# RF_AMPL_001.net
KiCad netlist of a schematic drawn in Altium Designer
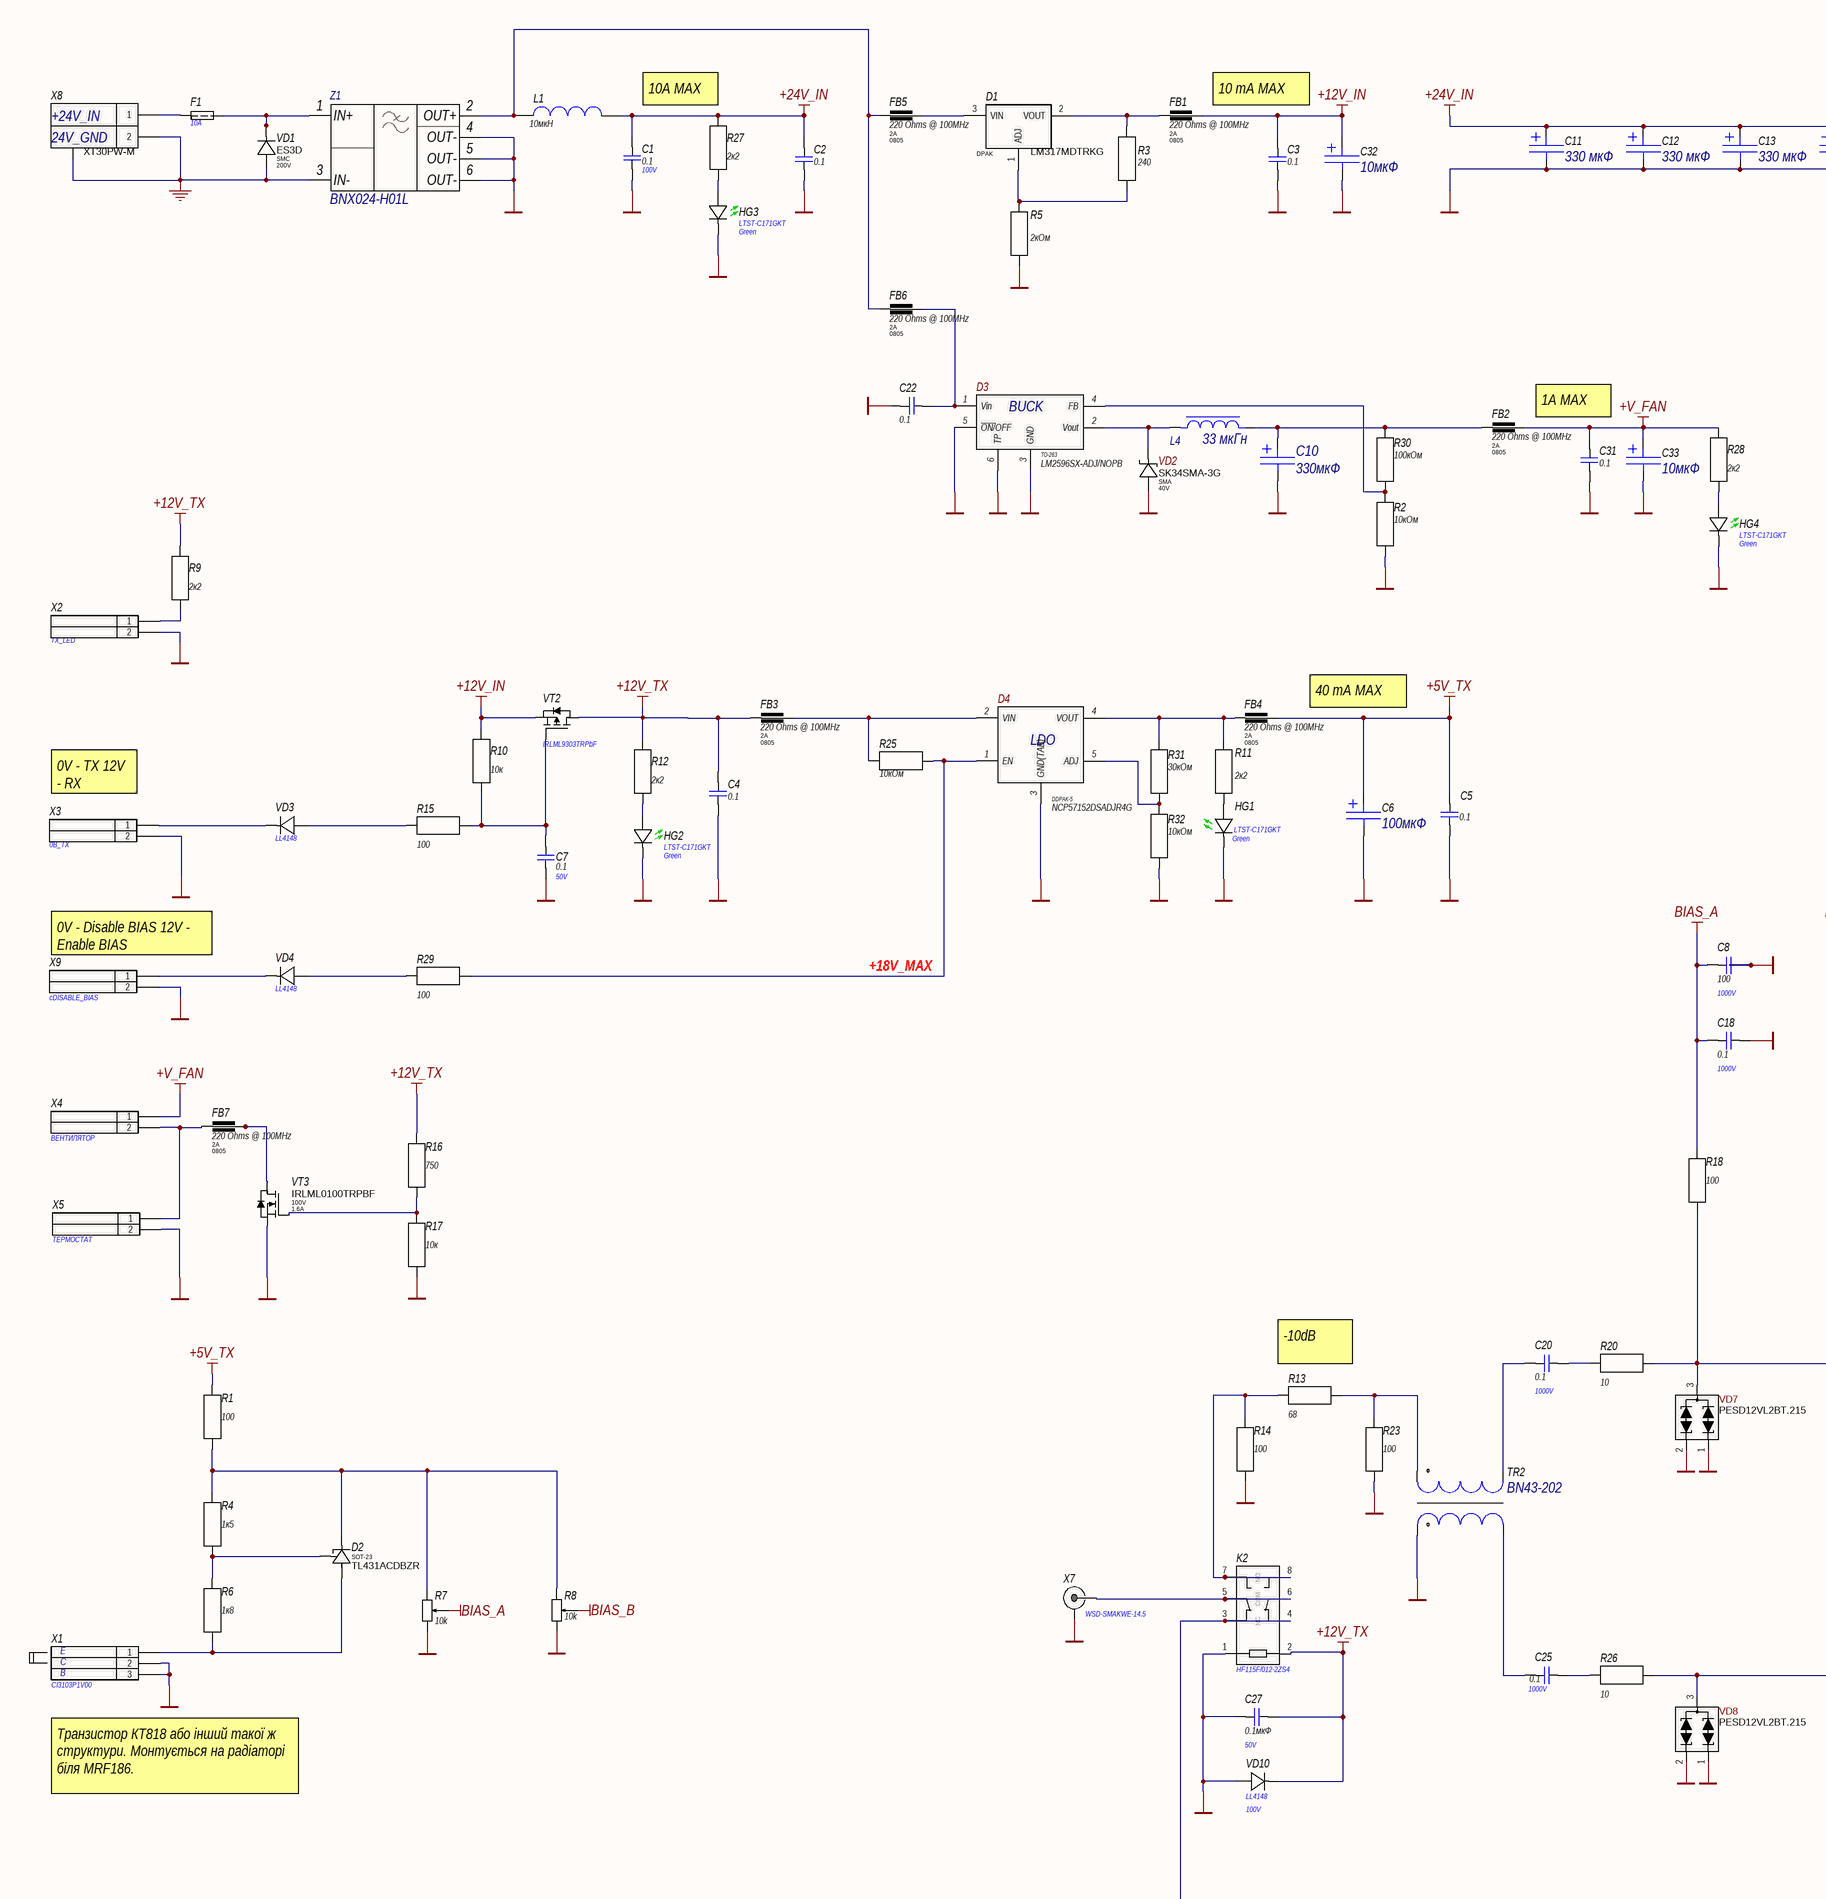
[diagram p0: RF_AMPL_001.SchDoc, left]
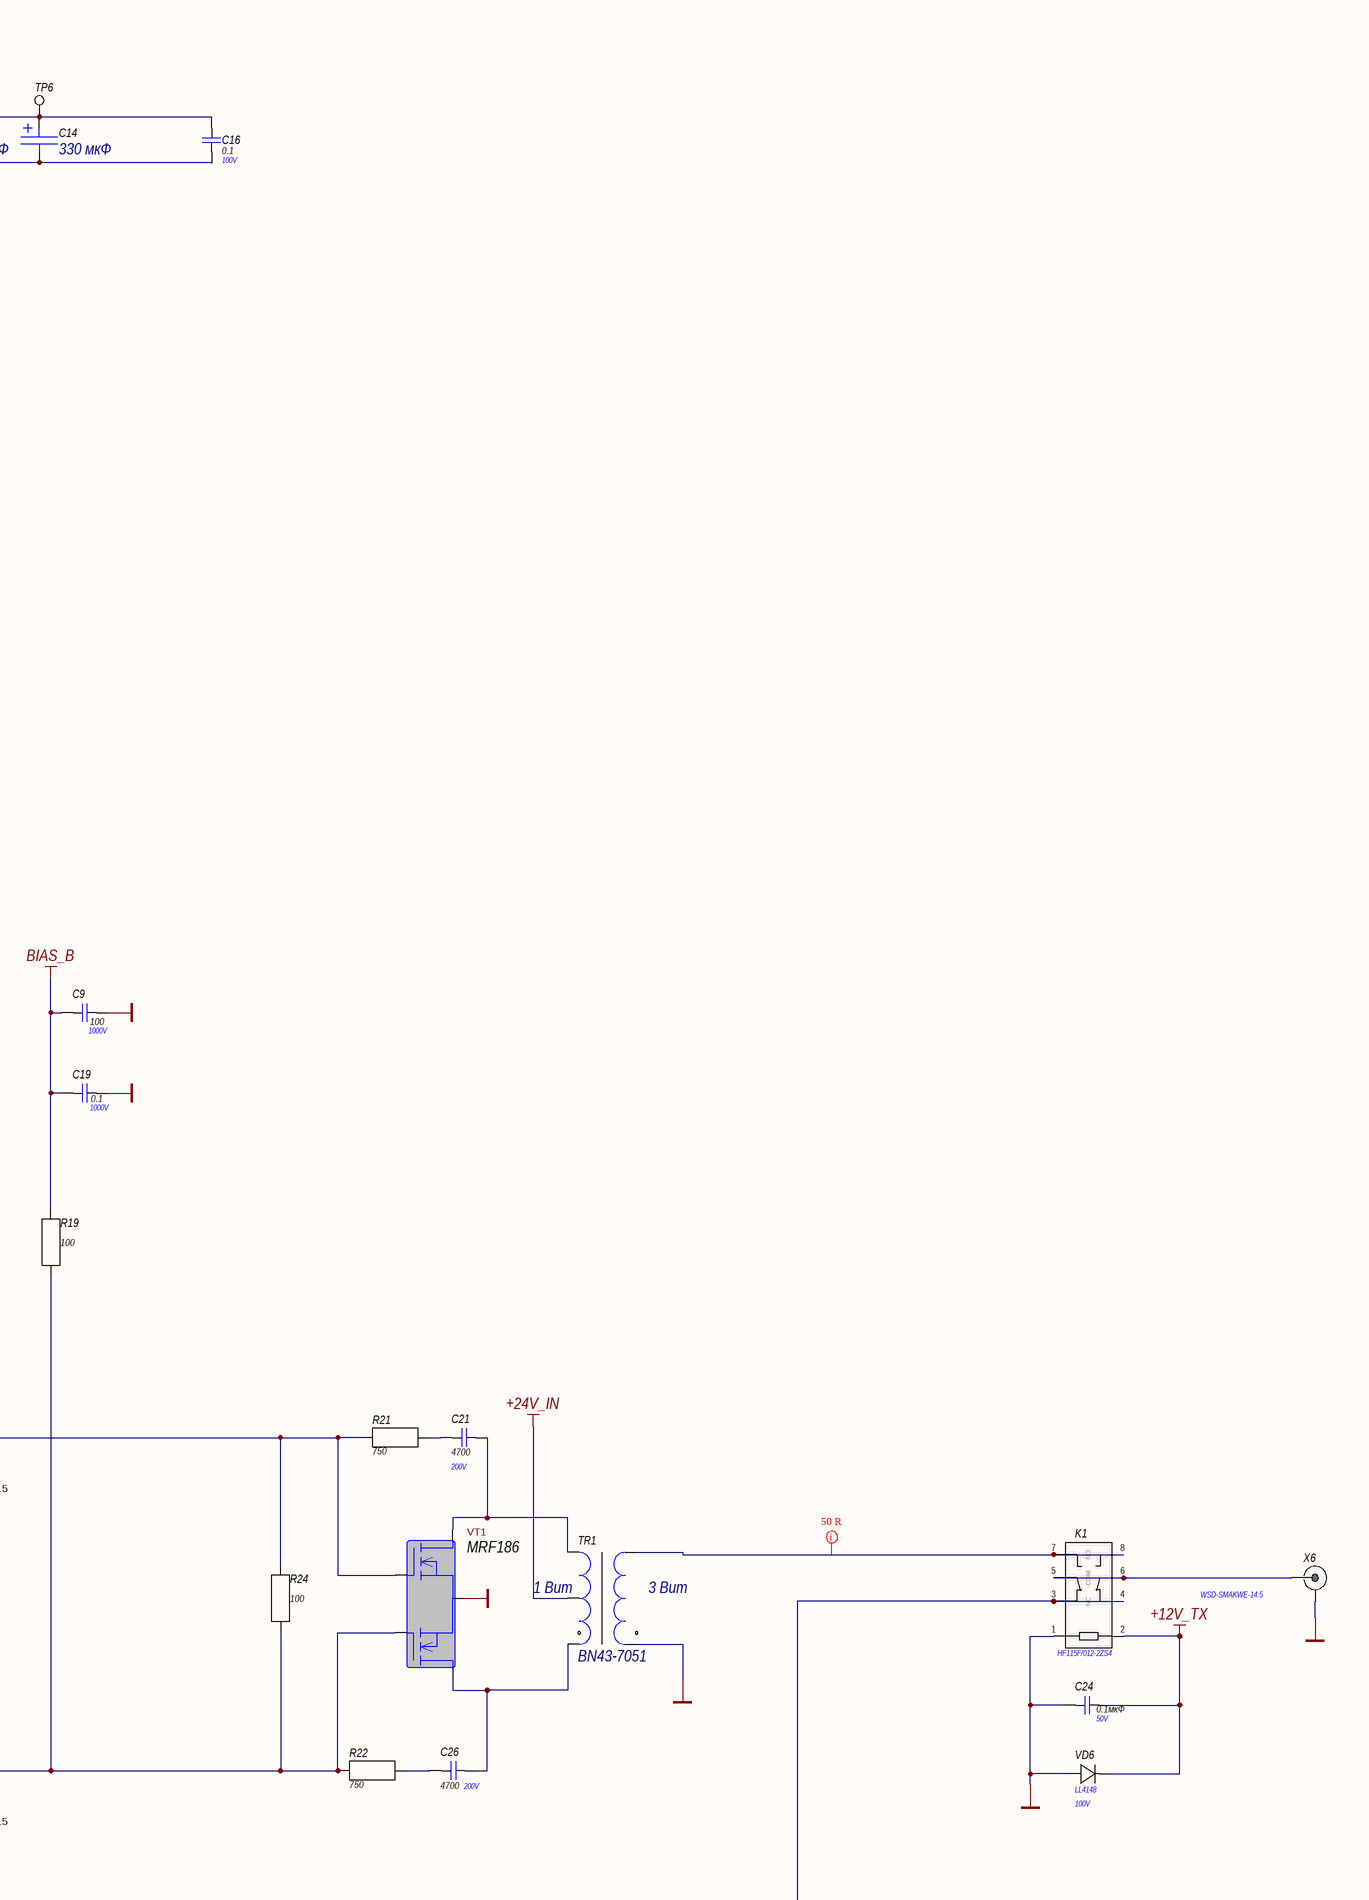
[diagram p1: RF_AMPL_001.SchDoc, right]

(export (version "E")
  (design (tool "Eeschema 10.0.6"))
  (components
    (comp (ref "C1")
      (value "0.1")
      (footprint "C_CERAMIC_1206_MED")
      (description "1nF 1000V X7R ±10% 1206 Ceramic Capacitor RoHS")
      (fields
        (field (name "VOLTAGE") "100V")
        (field (name "PART NUMBER") "1206B102K102CG")
        (field (name "MANUFACTURER") "Walsin")
      )
      (libsource (lib "vitech_capacitors") (part "1206B102K102CG"))
    )
    (comp (ref "C2")
      (value "0.1")
      (footprint "C_CERAMIC_1206_MED")
      (description "1nF 1000V X7R ±10% 1206 Ceramic Capacitor RoHS")
      (fields (field (name "VOLTAGE") "100V") (field (name "PART NUMBER") "1206B102K102CG"))
      (libsource (lib "vitech_capacitors") (part "1206B102K102CG"))
    )
    (comp (ref "C3")
      (value "0.1")
      (footprint "C_CERAMIC_1206_MED")
      (description "1nF 1000V X7R ±10% 1206 Ceramic Capacitor RoHS")
      (fields (field (name "VOLTAGE") "100V") (field (name "PART NUMBER") "1206B102K102CG"))
      (libsource (lib "vitech_capacitors") (part "1206B102K102CG"))
    )
    (comp (ref "C4")
      (value "0.1")
      (footprint "C_CERAMIC_1206_MED")
      (description "1nF 1000V X7R ±10% 1206 Ceramic Capacitor RoHS")
      (fields (field (name "VOLTAGE") "100V") (field (name "PART NUMBER") "1206B102K102CG"))
      (libsource (lib "vitech_capacitors") (part "1206B102K102CG"))
    )
    (comp (ref "C5")
      (value "0.1")
      (footprint "C_CERAMIC_1206_MED")
      (description "1nF 1000V X7R ±10% 1206 Ceramic Capacitor RoHS")
      (fields (field (name "VOLTAGE") "100V") (field (name "PART NUMBER") "1206B102K102CG"))
      (libsource (lib "vitech_capacitors") (part "1206B102K102CG"))
    )
    (comp (ref "C6")
      (value "100мкФ")
      (footprint "CAPM_CASE_D_7.3x4.3x3.1mm")
      (description "Capacitor Tantalum *pF ±*% *V Case D")
      (fields (field (name "MANUFACTURER") "AVX") (field (name "PART NUMBER") "TAJD107M016R"))
      (libsource (lib "Passive") (part "CAP_TANTALUM_POLAR_CASE_D"))
    )
    (comp (ref "C7")
      (value "0.1")
      (footprint "C_CERAMIC_1206_MED")
      (description "1nF 1000V X7R ±10% 1206 Ceramic Capacitor RoHS")
      (fields
        (field (name "VOLTAGE") "50V")
        (field (name "PART NUMBER") "1206B102K102CG")
        (field (name "MANUFACTURER") "Walsin")
      )
      (libsource (lib "vitech_capacitors") (part "1206B102K102CG"))
    )
    (comp (ref "C8")
      (value "100")
      (footprint "C_CERAMIC_1206_MED")
      (description "1nF 1000V X7R ±10% 1206 Ceramic Capacitor RoHS")
      (fields
        (field (name "VOLTAGE") "1000V")
        (field (name "PART NUMBER") "1206B102K102CG")
        (field (name "MANUFACTURER") "Walsin")
      )
      (libsource (lib "vitech_capacitors") (part "1206B102K102CG"))
    )
    (comp (ref "C9")
      (value "100")
      (footprint "C_CERAMIC_1206_MED")
      (description "1nF 1000V X7R ±10% 1206 Ceramic Capacitor RoHS")
      (fields
        (field (name "VOLTAGE") "1000V")
        (field (name "PART NUMBER") "1206B102K102CG")
        (field (name "MANUFACTURER") "Walsin")
      )
      (libsource (lib "vitech_capacitors") (part "1206B102K102CG"))
    )
    (comp (ref "C10")
      (value "330мкФ")
      (footprint "CAPA_CASE_F_Panasonic_FT")
      (description "Capacitor Electrolytic *pF ±*% *V Case F")
      (fields (field (name "MANUFACTURER") "Panasonic") (field (name "PART NUMBER") "EEEFK1C331P"))
      (libsource (lib "Passive") (part "CAP_ELECTROLYTIC_POLAR_CASE_F_Panasonic_FT"))
    )
    (comp (ref "C11")
      (value "330 мкФ")
      (footprint "CAPA_CASE_G_10.4x10.4x10.5mm")
      (description "Capacitor Electrolytic *pF ±*% *V Case G")
      (fields (field (name "TOLERANCE") "±*%") (field (name "VOLTAGE") "*В"))
      (libsource (lib "Passive") (part "CAP_ELECTROLYTIC_POLAR_CASE_G"))
    )
    (comp (ref "C12")
      (value "330 мкФ")
      (footprint "CAPA_CASE_G_10.4x10.4x10.5mm")
      (description "Capacitor Electrolytic *pF ±*% *V Case G")
      (fields (field (name "TOLERANCE") "±*%") (field (name "VOLTAGE") "*В"))
      (libsource (lib "Passive") (part "CAP_ELECTROLYTIC_POLAR_CASE_G"))
    )
    (comp (ref "C13")
      (value "330 мкФ")
      (footprint "CAPA_CASE_G_10.4x10.4x10.5mm")
      (description "Capacitor Electrolytic *pF ±*% *V Case G")
      (fields (field (name "TOLERANCE") "±*%") (field (name "VOLTAGE") "*В"))
      (libsource (lib "Passive") (part "CAP_ELECTROLYTIC_POLAR_CASE_G"))
    )
    (comp (ref "C14")
      (value "330 мкФ")
      (footprint "CAPA_CASE_G_10.4x10.4x10.5mm")
      (description "Capacitor Electrolytic *pF ±*% *V Case G")
      (fields (field (name "TOLERANCE") "±*%") (field (name "VOLTAGE") "*В"))
      (libsource (lib "Passive") (part "CAP_ELECTROLYTIC_POLAR_CASE_G"))
    )
    (comp (ref "C16")
      (value "0.1")
      (footprint "C_CERAMIC_1206_MED")
      (description "1nF 1000V X7R ±10% 1206 Ceramic Capacitor RoHS")
      (fields
        (field (name "VOLTAGE") "100V")
        (field (name "PART NUMBER") "1206B102K102CG")
        (field (name "MANUFACTURER") "Walsin")
      )
      (libsource (lib "vitech_capacitors") (part "1206B102K102CG"))
    )
    (comp (ref "C18")
      (value "0.1")
      (footprint "C_CERAMIC_1206_MED")
      (description "1nF 1000V X7R ±10% 1206 Ceramic Capacitor RoHS")
      (fields
        (field (name "VOLTAGE") "1000V")
        (field (name "PART NUMBER") "1206B102K102CG")
        (field (name "MANUFACTURER") "Walsin")
      )
      (libsource (lib "vitech_capacitors") (part "1206B102K102CG"))
    )
    (comp (ref "C19")
      (value "0.1")
      (footprint "C_CERAMIC_1206_MED")
      (description "1nF 1000V X7R ±10% 1206 Ceramic Capacitor RoHS")
      (fields
        (field (name "VOLTAGE") "1000V")
        (field (name "PART NUMBER") "1206B102K102CG")
        (field (name "MANUFACTURER") "Walsin")
      )
      (libsource (lib "vitech_capacitors") (part "1206B102K102CG"))
    )
    (comp (ref "C20")
      (value "0.1")
      (footprint "C_CERAMIC_1206_MED")
      (description "1nF 1000V X7R ±10% 1206 Ceramic Capacitor RoHS")
      (fields
        (field (name "VOLTAGE") "1000V")
        (field (name "PART NUMBER") "1206B102K102CG")
        (field (name "MANUFACTURER") "Walsin")
      )
      (libsource (lib "vitech_capacitors") (part "1206B102K102CG"))
    )
    (comp (ref "C21")
      (value "4700")
      (footprint "C_CERAMIC_1206_MED")
      (description "1nF 1000V X7R ±10% 1206 Ceramic Capacitor RoHS")
      (fields
        (field (name "VOLTAGE") "200V")
        (field (name "PART NUMBER") "12065A472JAT2A")
        (field (name "MANUFACTURER") "Walsin")
      )
      (libsource (lib "vitech_capacitors") (part "1206B102K102CG"))
    )
    (comp (ref "C22")
      (value "0.1")
      (footprint "C_CERAMIC_1206_MED")
      (description "1nF 1000V X7R ±10% 1206 Ceramic Capacitor RoHS")
      (fields (field (name "VOLTAGE") "100V") (field (name "PART NUMBER") "1206B102K102CG"))
      (libsource (lib "vitech_capacitors") (part "1206B102K102CG"))
    )
    (comp (ref "C24")
      (value "0.1мкФ")
      (footprint "C_CERAMIC_0805_HI")
      (fields
        (field (name "PART NUMBER") "**")
        (field (name "MANUFACTURER") "Hitano")
        (field (name "TOLERANCE") "±5%")
        (field (name "VOLTAGE") "50V")
      )
      (libsource (lib "vitech_capacitors") (part "CERAMIC_0805"))
    )
    (comp (ref "C25")
      (value "0.1")
      (footprint "C_CERAMIC_1206_MED")
      (description "1nF 1000V X7R ±10% 1206 Ceramic Capacitor RoHS")
      (fields
        (field (name "VOLTAGE") "1000V")
        (field (name "PART NUMBER") "1206B102K102CG")
        (field (name "MANUFACTURER") "Walsin")
      )
      (libsource (lib "vitech_capacitors") (part "1206B102K102CG"))
    )
    (comp (ref "C26")
      (value "4700")
      (footprint "C_CERAMIC_1206_MED")
      (description "1nF 1000V X7R ±10% 1206 Ceramic Capacitor RoHS")
      (fields
        (field (name "VOLTAGE") "200V")
        (field (name "PART NUMBER") "12065A472JAT2A")
        (field (name "MANUFACTURER") "Walsin")
      )
      (libsource (lib "vitech_capacitors") (part "1206B102K102CG"))
    )
    (comp (ref "C27")
      (value "0.1мкФ")
      (footprint "C_CERAMIC_0805_HI")
      (fields
        (field (name "PART NUMBER") "**")
        (field (name "MANUFACTURER") "Hitano")
        (field (name "TOLERANCE") "±5%")
        (field (name "VOLTAGE") "50V")
      )
      (libsource (lib "vitech_capacitors") (part "CERAMIC_0805"))
    )
    (comp (ref "C31")
      (value "0.1")
      (footprint "C_CERAMIC_1206_MED")
      (description "1nF 1000V X7R ±10% 1206 Ceramic Capacitor RoHS")
      (fields (field (name "VOLTAGE") "100V") (field (name "PART NUMBER") "1206B102K102CG"))
      (libsource (lib "vitech_capacitors") (part "1206B102K102CG"))
    )
    (comp (ref "C32")
      (value "10мкФ")
      (footprint "CAPM_CASE_B_3.5x2.8x2.1mm")
      (description "Capacitor Tantalum *pF ±*% *V Case B")
      (fields (field (name "TOLERANCE") "±*%") (field (name "VOLTAGE") "20"))
      (libsource (lib "Passive") (part "CAP_TANTALUM_POLAR_CASE_B"))
    )
    (comp (ref "C33")
      (value "10мкФ")
      (footprint "CAPM_CASE_B_3.5x2.8x2.1mm")
      (description "Capacitor Tantalum *pF ±*% *V Case B")
      (fields (field (name "TOLERANCE") "±*%") (field (name "VOLTAGE") "20"))
      (libsource (lib "Passive") (part "CAP_TANTALUM_POLAR_CASE_B"))
    )
    (comp (ref "D1")
      (value "LM317MDTRKG")
      (footprint "DPAK")
      (description "4.25V to 40V Input Linear Voltage Regulator, 1 Output 500mA, Adjustable, TO-252-3 (DPAK)")
      (fields
        (field (name "MANUFACTURER") "Onsemi")
        (field (name "PACKAGE") "DPAK")
        (field (name "PART NUMBER") "LM317MDTRKG")
      )
      (libsource (lib "vitech_ic") (part "LM317MDTRKG"))
    )
    (comp (ref "D2")
      (value "TL431ACDBZR")
      (footprint "SOT-23_MED")
      (description "Adjustable Precision Shunt Regulator, Accuracy 1%,  SOT-23-3")
      (fields
        (field (name "PACKAGE") "SOT-23")
        (field (name "PART NUMBER") "TL431ACDBZR")
        (field (name "MANUFACTURER") "Texas Instruments")
      )
      (libsource (lib "vitech_ic") (part "TL431ACDBZR"))
    )
    (comp (ref "D3")
      (value "LM2596SX-ADJ/NOPB")
      (footprint "TO-263-5-1")
      (description "SIMPLE SWITCHER Power Converter 150-kHz 3-A Step-Down Voltage Regulator")
      (fields
        (field (name "MANUFACTURER") "Texas Instruments")
        (field (name "PACKAGE") "TO-263")
        (field (name "PART NUMBER") "LM2596SX-ADJ/NOPB")
      )
      (libsource (lib "vitech_ic") (part "LM2596SX-ADJ/NOPB"))
    )
    (comp (ref "D4")
      (value "NCP57152DSADJR4G")
      (footprint "DDPAK-5")
      (description "1.24V to 13V Input Low Dropout Regulator, Adjustable, 1.5A, D2PAK-5")
      (fields
        (field (name "PACKAGE") "DDPAK-5")
        (field (name "PART NUMBER") "NCP57152DSADJR4G")
        (field (name "MANUFACTURER") "Onsemi")
      )
      (libsource (lib "vitech_ic") (part "NCP57152DSADJR4G"))
    )
    (comp (ref "F1")
      (value "STANDART_FUSE_HOLDER")
      (footprint "17861640001")
      (description "Automotive Fuse holder THT-Mount")
      (fields (field (name "MANUFACTURER_PART_NUMBER") "17861640001") (field (name "CURRENT") "10A"))
      (libsource (lib "vitech_fuses") (part "STANDART_FUSE_HOLDER"))
    )
    (comp (ref "FB1")
      (value "220 Ohms @ 100MHz")
      (footprint "BLM21PGxxxxN1-Series")
      (description "220 Ohms @ 100MHz Power Line Ferrite Bead 0805, 2A 45mOhm")
      (fields
        (field (name "CURRENT") "2A")
        (field (name "PACKAGE") "0805")
        (field (name "PART NUMBER") "BLM21PG221SN1D")
        (field (name "TOLERANCE") "±25%")
      )
      (libsource (lib "vitech_inductors") (part "BLM21PG221SN1D"))
    )
    (comp (ref "FB2")
      (value "220 Ohms @ 100MHz")
      (footprint "BLM21PGxxxxN1-Series")
      (description "220 Ohms @ 100MHz Power Line Ferrite Bead 0805, 2A 45mOhm")
      (fields
        (field (name "CURRENT") "2A")
        (field (name "PACKAGE") "0805")
        (field (name "PART NUMBER") "BLM21PG221SN1D")
        (field (name "TOLERANCE") "±25%")
      )
      (libsource (lib "vitech_inductors") (part "BLM21PG221SN1D"))
    )
    (comp (ref "FB3")
      (value "220 Ohms @ 100MHz")
      (footprint "BLM21PGxxxxN1-Series")
      (description "220 Ohms @ 100MHz Power Line Ferrite Bead 0805, 2A 45mOhm")
      (fields
        (field (name "CURRENT") "2A")
        (field (name "PACKAGE") "0805")
        (field (name "PART NUMBER") "BLM21PG221SN1D")
        (field (name "TOLERANCE") "±25%")
      )
      (libsource (lib "vitech_inductors") (part "BLM21PG221SN1D"))
    )
    (comp (ref "FB4")
      (value "220 Ohms @ 100MHz")
      (footprint "BLM21PGxxxxN1-Series")
      (description "220 Ohms @ 100MHz Power Line Ferrite Bead 0805, 2A 45mOhm")
      (fields
        (field (name "CURRENT") "2A")
        (field (name "PACKAGE") "0805")
        (field (name "PART NUMBER") "BLM21PG221SN1D")
        (field (name "TOLERANCE") "±25%")
      )
      (libsource (lib "vitech_inductors") (part "BLM21PG221SN1D"))
    )
    (comp (ref "FB5")
      (value "220 Ohms @ 100MHz")
      (footprint "BLM21PGxxxxN1-Series")
      (description "220 Ohms @ 100MHz Power Line Ferrite Bead 0805, 2A 45mOhm")
      (fields
        (field (name "CURRENT") "2A")
        (field (name "PACKAGE") "0805")
        (field (name "PART NUMBER") "BLM21PG221SN1D")
        (field (name "TOLERANCE") "±25%")
      )
      (libsource (lib "vitech_inductors") (part "BLM21PG221SN1D"))
    )
    (comp (ref "FB6")
      (value "220 Ohms @ 100MHz")
      (footprint "BLM21PGxxxxN1-Series")
      (description "220 Ohms @ 100MHz Power Line Ferrite Bead 0805, 2A 45mOhm")
      (fields
        (field (name "CURRENT") "2A")
        (field (name "PACKAGE") "0805")
        (field (name "PART NUMBER") "BLM21PG221SN1D")
        (field (name "TOLERANCE") "±25%")
      )
      (libsource (lib "vitech_inductors") (part "BLM21PG221SN1D"))
    )
    (comp (ref "FB7")
      (value "220 Ohms @ 100MHz")
      (footprint "BLM21PGxxxxN1-Series")
      (description "220 Ohms @ 100MHz Power Line Ferrite Bead 0805, 2A 45mOhm")
      (fields
        (field (name "CURRENT") "2A")
        (field (name "PACKAGE") "0805")
        (field (name "PART NUMBER") "BLM21PG221SN1D")
        (field (name "TOLERANCE") "±25%")
      )
      (libsource (lib "vitech_inductors") (part "BLM21PG221SN1D"))
    )
    (comp (ref "HG1")
      (value "LTST-C171GKT")
      (footprint "LTST-C171GKT")
      (description "Low Power LED, Green 565nm, Clear, SMD 0805, Vf 2.1V - 2.6V, 5 ~ 12mcd @ 20 mA, 130°")
      (fields
        (field (name "PART NUMBER") "LTST-C171GKT")
        (field (name "COLOR") "Green")
        (field (name "MANUFACTURER") "Lite-On Optoelectronics")
      )
      (libsource (lib "vitech_opto") (part "LTST-C171GKT"))
    )
    (comp (ref "HG2")
      (value "LTST-C171GKT")
      (footprint "LTST-C171GKT")
      (description "Low Power LED, Green 565nm, Clear, SMD 0805, Vf 2.1V - 2.6V, 5 ~ 12mcd @ 20 mA, 130°")
      (fields
        (field (name "PART NUMBER") "LTST-C171GKT")
        (field (name "COLOR") "Green")
        (field (name "MANUFACTURER") "Lite-On Optoelectronics")
      )
      (libsource (lib "vitech_opto") (part "LTST-C171GKT"))
    )
    (comp (ref "HG3")
      (value "LTST-C171GKT")
      (footprint "LTST-C171GKT")
      (description "Low Power LED, Green 565nm, Clear, SMD 0805, Vf 2.1V - 2.6V, 5 ~ 12mcd @ 20 mA, 130°")
      (fields
        (field (name "PART NUMBER") "LTST-C171GKT")
        (field (name "COLOR") "Green")
        (field (name "MANUFACTURER") "Lite-On Optoelectronics")
      )
      (libsource (lib "vitech_opto") (part "LTST-C171GKT"))
    )
    (comp (ref "HG4")
      (value "LTST-C171GKT")
      (footprint "LTST-C171GKT")
      (description "Low Power LED, Green 565nm, Clear, SMD 0805, Vf 2.1V - 2.6V, 5 ~ 12mcd @ 20 mA, 130°")
      (fields
        (field (name "PART NUMBER") "LTST-C171GKT")
        (field (name "COLOR") "Green")
        (field (name "MANUFACTURER") "Lite-On Optoelectronics")
      )
      (libsource (lib "vitech_opto") (part "LTST-C171GKT"))
    )
    (comp (ref "K1")
      (value "HF115F/012-2ZS4")
      (footprint "HF115Fxxx-1(2)Zx3(4)")
      (description "Miniature High Power Relay, DPDT (2 Form C), 12VDC 400mW Coil, 5.0mm 2 Pole 8A AgCdO")
      (fields (field (name "PART NUMBER") "HF115F/012-2ZS4") (field (name "MANUFACTURER") "Hongfa"))
      (libsource (lib "vitech_electromechanics") (part "HF115F/012-2ZS4"))
    )
    (comp (ref "K2")
      (value "HF115F/012-2ZS4")
      (footprint "HF115Fxxx-1(2)Zx3(4)")
      (description "Miniature High Power Relay, DPDT (2 Form C), 12VDC 400mW Coil, 5.0mm 2 Pole 8A AgCdO")
      (fields (field (name "PART NUMBER") "HF115F/012-2ZS4") (field (name "MANUFACTURER") "Hongfa"))
      (libsource (lib "vitech_electromechanics") (part "HF115F/012-2ZS4"))
    )
    (comp (ref "L1")
      (value "10мкH")
      (footprint "IND: R22.9/14/7.62 (H)")
      (fields
        (field (name "MANUFACTURER") "Magnetics")
        (field (name "PARTNUMBER") "0077310A7")
        (field (name "VALUEMANUFACTURERPARTNUMBER") "Fixed inductor, 10мкH, ±20%, R22.9/14/7.62, Kool Mu, µ=125, 90 нГн/витков2")
      )
      (libsource (lib "inductor") (part "Inductor_R22.9/14/7.62"))
    )
    (comp (ref "L4")
      (value "33 мкГн")
      (footprint "INDPWR_Sumida_CDRH127/LD_INDM120120X80N")
      (description "FIXED IND  UH   A  MOHM SMD")
      (fields (field (name "MANUFACTURER") "Sumida") (field (name "PART NUMBER") "CDRH127/LD"))
      (libsource (lib "Passive") (part "INDPWR_Sumida_CDRH127/LD"))
    )
    (comp (ref "R1")
      (value "100")
      (footprint "R_ANY_CHIP_0805_HI")
      (description "RES 0.47 OHM 1% 1/8W 0805")
      (fields
        (field (name "MANUFACTURER") "Panasonic Electronic Components")
        (field (name "PART NUMBER") "ERJ-3RQFR47V")
      )
      (libsource (lib "") (part "RES_0805_2"))
    )
    (comp (ref "R2")
      (value "10кОм")
      (footprint "R_ANY_CHIP_0805_HI")
      (description "RES 0.47 OHM 1% 1/8W 0805")
      (fields
        (field (name "MANUFACTURER") "Panasonic Electronic Components")
        (field (name "PART NUMBER") "ERJ-3RQFR47V")
      )
      (libsource (lib "") (part "RES_0805_2"))
    )
    (comp (ref "R3")
      (value "240")
      (footprint "R_ANY_CHIP_0805_HI")
      (description "RES 0.47 OHM 1% 1/8W 0805")
      (fields
        (field (name "MANUFACTURER") "Panasonic Electronic Components")
        (field (name "PART NUMBER") "ERJ-3RQFR47V")
      )
      (libsource (lib "") (part "RES_0805_3"))
    )
    (comp (ref "R4")
      (value "1к5")
      (footprint "R_ANY_CHIP_0805_HI")
      (description "RES 0.47 OHM 1% 1/8W 0805")
      (fields
        (field (name "MANUFACTURER") "Panasonic Electronic Components")
        (field (name "PART NUMBER") "ERJ-3RQFR47V")
      )
      (libsource (lib "") (part "RES_0805_2"))
    )
    (comp (ref "R5")
      (value "2кОм")
      (footprint "R_ANY_CHIP_0805_HI")
      (description "RES 0.47 OHM 1% 1/8W 0805")
      (fields
        (field (name "MANUFACTURER") "Panasonic Electronic Components")
        (field (name "PART NUMBER") "ERJ-3RQFR47V")
      )
      (libsource (lib "") (part "RES_0805_3"))
    )
    (comp (ref "R6")
      (value "1к8")
      (footprint "R_ANY_CHIP_0805_HI")
      (description "RES 0.47 OHM 1% 1/8W 0805")
      (fields
        (field (name "MANUFACTURER") "Panasonic Electronic Components")
        (field (name "PART NUMBER") "ERJ-3RQFR47V")
      )
      (libsource (lib "") (part "RES_0805_2"))
    )
    (comp (ref "R7")
      (value "10k")
      (footprint "3296W-1-xxx")
      (description "10 kOhms ±10% Trimmer Resistor, 0.5W, Through Hole 3/8\", 4.83x9.53mm, 10.03mm Height")
      (fields (field (name "TOLERANCE") "±10%") (field (name "PART NUMBER") "3296W-1-103LF"))
      (libsource (lib "resistors") (part "3296W-1-103LF"))
    )
    (comp (ref "R8")
      (value "10k")
      (footprint "3296W-1-xxx")
      (description "10 kOhms ±10% Trimmer Resistor, 0.5W, Through Hole 3/8\", 4.83x9.53mm, 10.03mm Height")
      (fields (field (name "TOLERANCE") "±10%") (field (name "PART NUMBER") "3296W-1-103LF"))
      (libsource (lib "resistors") (part "3296W-1-103LF"))
    )
    (comp (ref "R9")
      (value "2к2")
      (footprint "R_ANY_CHIP_0805_HI")
      (description "RES 0.47 OHM 1% 1/8W 0805")
      (fields
        (field (name "MANUFACTURER") "Panasonic Electronic Components")
        (field (name "PART NUMBER") "ERJ-3RQFR47V")
      )
      (libsource (lib "") (part "RES_0805_3"))
    )
    (comp (ref "R10")
      (value "10к")
      (footprint "R_ANY_CHIP_0805_HI")
      (description "RES 0.47 OHM 1% 1/8W 0805")
      (fields
        (field (name "MANUFACTURER") "Panasonic Electronic Components")
        (field (name "PART NUMBER") "ERJ-3RQFR47V")
      )
      (libsource (lib "") (part "RES_0805_3"))
    )
    (comp (ref "R11")
      (value "2к2")
      (footprint "R_ANY_CHIP_0805_HI")
      (description "RES 0.47 OHM 1% 1/8W 0805")
      (fields
        (field (name "MANUFACTURER") "Panasonic Electronic Components")
        (field (name "PART NUMBER") "ERJ-3RQFR47V")
      )
      (libsource (lib "") (part "RES_0805_3"))
    )
    (comp (ref "R12")
      (value "2к2")
      (footprint "R_ANY_CHIP_0805_HI")
      (description "RES 0.47 OHM 1% 1/8W 0805")
      (fields
        (field (name "MANUFACTURER") "Panasonic Electronic Components")
        (field (name "PART NUMBER") "ERJ-3RQFR47V")
      )
      (libsource (lib "") (part "RES_0805_2"))
    )
    (comp (ref "R13")
      (value "68")
      (footprint "FKN2WS-Series")
      (description "RESISTORS THT")
      (fields
        (field (name "MANUFACTURER") "Panasonic Electronic Components")
        (field (name "PART NUMBER") "ERJ-3RQFR47V")
      )
      (libsource (lib "") (part "RES_THT_1"))
    )
    (comp (ref "R14")
      (value "100")
      (footprint "FKN2WS-Series")
      (description "RESISTORS THT")
      (fields
        (field (name "MANUFACTURER") "Panasonic Electronic Components")
        (field (name "PART NUMBER") "ERJ-3RQFR47V")
      )
      (libsource (lib "") (part "RES_THT_2"))
    )
    (comp (ref "R15")
      (value "100")
      (footprint "R_ANY_CHIP_0805_HI")
      (description "RES 0.47 OHM 1% 1/8W 0805")
      (fields
        (field (name "MANUFACTURER") "Panasonic Electronic Components")
        (field (name "PART NUMBER") "ERJ-3RQFR47V")
      )
      (libsource (lib "") (part "RES_0805_1"))
    )
    (comp (ref "R16")
      (value "750")
      (footprint "R_ANY_CHIP_0805_HI")
      (description "RES 0.47 OHM 1% 1/8W 0805")
      (fields
        (field (name "MANUFACTURER") "Panasonic Electronic Components")
        (field (name "PART NUMBER") "ERJ-3RQFR47V")
      )
      (libsource (lib "") (part "RES_0805_2"))
    )
    (comp (ref "R17")
      (value "10к")
      (footprint "R_ANY_CHIP_0805_HI")
      (description "RES 0.47 OHM 1% 1/8W 0805")
      (fields
        (field (name "MANUFACTURER") "Panasonic Electronic Components")
        (field (name "PART NUMBER") "ERJ-3RQFR47V")
      )
      (libsource (lib "") (part "RES_0805_3"))
    )
    (comp (ref "R18")
      (value "100")
      (footprint "R_ANY_CHIP_0805_HI")
      (description "RES 0.47 OHM 1% 1/8W 0805")
      (fields
        (field (name "MANUFACTURER") "Panasonic Electronic Components")
        (field (name "PART NUMBER") "ERJ-3RQFR47V")
      )
      (libsource (lib "") (part "RES_0805_2"))
    )
    (comp (ref "R19")
      (value "100")
      (footprint "R_ANY_CHIP_0805_HI")
      (description "RES 0.47 OHM 1% 1/8W 0805")
      (fields
        (field (name "MANUFACTURER") "Panasonic Electronic Components")
        (field (name "PART NUMBER") "ERJ-3RQFR47V")
      )
      (libsource (lib "") (part "RES_0805_2"))
    )
    (comp (ref "R20")
      (value "10")
      (footprint "R_ANY_CHIP_0805_HI")
      (description "RES 0.47 OHM 1% 1/8W 0805")
      (fields
        (field (name "MANUFACTURER") "Panasonic Electronic Components")
        (field (name "PART NUMBER") "ERJ-3RQFR47V")
      )
      (libsource (lib "vitech_resistors") (part "RES_0805"))
    )
    (comp (ref "R21")
      (value "750")
      (footprint "FKN2WS-Series")
      (description "RESISTORS THT")
      (fields
        (field (name "MANUFACTURER") "Panasonic Electronic Components")
        (field (name "PART NUMBER") "ERJ-3RQFR47V")
      )
      (libsource (lib "vitech_resistors") (part "RES_THT"))
    )
    (comp (ref "R22")
      (value "750")
      (footprint "FKN2WS-Series")
      (description "RESISTORS THT")
      (fields
        (field (name "MANUFACTURER") "Panasonic Electronic Components")
        (field (name "PART NUMBER") "ERJ-3RQFR47V")
      )
      (libsource (lib "vitech_resistors") (part "RES_THT"))
    )
    (comp (ref "R23")
      (value "100")
      (footprint "FKN2WS-Series")
      (description "RESISTORS THT")
      (fields
        (field (name "MANUFACTURER") "Panasonic Electronic Components")
        (field (name "PART NUMBER") "ERJ-3RQFR47V")
      )
      (libsource (lib "") (part "RES_THT_2"))
    )
    (comp (ref "R24")
      (value "100")
      (footprint "FKN2WS-Series")
      (description "RESISTORS THT")
      (fields
        (field (name "MANUFACTURER") "Panasonic Electronic Components")
        (field (name "PART NUMBER") "ERJ-3RQFR47V")
      )
      (libsource (lib "") (part "RES_THT_2"))
    )
    (comp (ref "R25")
      (value "10кОм")
      (footprint "R_ANY_CHIP_0805_HI")
      (description "RES 0.47 OHM 1% 1/8W 0805")
      (fields
        (field (name "MANUFACTURER") "Panasonic Electronic Components")
        (field (name "PART NUMBER") "ERJ-3RQFR47V")
      )
      (libsource (lib "vitech_resistors") (part "RES_0805"))
    )
    (comp (ref "R26")
      (value "10")
      (footprint "R_ANY_CHIP_0805_HI")
      (description "RES 0.47 OHM 1% 1/8W 0805")
      (fields
        (field (name "MANUFACTURER") "Panasonic Electronic Components")
        (field (name "PART NUMBER") "ERJ-3RQFR47V")
      )
      (libsource (lib "vitech_resistors") (part "RES_0805"))
    )
    (comp (ref "R27")
      (value "2к2")
      (footprint "R_ANY_CHIP_0805_HI")
      (description "RES 0.47 OHM 1% 1/8W 0805")
      (fields
        (field (name "MANUFACTURER") "Panasonic Electronic Components")
        (field (name "PART NUMBER") "ERJ-3RQFR47V")
      )
      (libsource (lib "") (part "RES_0805_2"))
    )
    (comp (ref "R28")
      (value "2к2")
      (footprint "R_ANY_CHIP_0805_HI")
      (description "RES 0.47 OHM 1% 1/8W 0805")
      (fields
        (field (name "MANUFACTURER") "Panasonic Electronic Components")
        (field (name "PART NUMBER") "ERJ-3RQFR47V")
      )
      (libsource (lib "") (part "RES_0805_2"))
    )
    (comp (ref "R29")
      (value "100")
      (footprint "R_ANY_CHIP_0805_HI")
      (description "RES 0.47 OHM 1% 1/8W 0805")
      (fields
        (field (name "MANUFACTURER") "Panasonic Electronic Components")
        (field (name "PART NUMBER") "ERJ-3RQFR47V")
      )
      (libsource (lib "") (part "RES_0805_1"))
    )
    (comp (ref "R30")
      (value "100кОм")
      (footprint "R_ANY_CHIP_0805_HI")
      (description "100кОм 1% 1/8W 0805")
      (fields
        (field (name "MANUFACTURER") "Panasonic Electronic Components")
        (field (name "PART NUMBER") "ERJ-3RQFR47V")
      )
      (libsource (lib "") (part "RES_0805_2"))
    )
    (comp (ref "R31")
      (value "30кОм")
      (footprint "R_ANY_CHIP_0805_HI")
      (description "RES 0.47 OHM 1% 1/8W 0805")
      (fields
        (field (name "MANUFACTURER") "Panasonic Electronic Components")
        (field (name "PART NUMBER") "ERJ-3RQFR47V")
      )
      (libsource (lib "") (part "RES_0805_2"))
    )
    (comp (ref "R32")
      (value "10кОм")
      (footprint "R_ANY_CHIP_0805_HI")
      (description "RES 0.47 OHM 1% 1/8W 0805")
      (fields
        (field (name "MANUFACTURER") "Panasonic Electronic Components")
        (field (name "PART NUMBER") "ERJ-3RQFR47V")
      )
      (libsource (lib "") (part "RES_0805_2"))
    )
    (comp (ref "TP6")
      (value "PAD-1.75mm")
      (footprint "PAD-1.75mm")
      (description "1.75mm Pad for Plug-In or Receptacle")
      (fields (field (name "MANUFACTURER") "NONE"))
      (libsource (lib "probetools") (part "PAD-1.75mm"))
    )
    (comp (ref "TR1")
      (value "TR")
      (footprint "Amidon_43-7051")
      (fields
        (field (name "MANUFACTURER") "Handmade")
        (field (name "TOLERANCE") "±20%")
        (field (name "PART NUMBER") "BN43-7051")
      )
      (libsource (lib "vitech_inductors") (part "Amidon_BN43-7051"))
    )
    (comp (ref "TR2")
      (value "TR")
      (footprint "Amidon_43-202")
      (fields
        (field (name "MANUFACTURER") "Handmade")
        (field (name "TOLERANCE") "±20%")
        (field (name "PART NUMBER") "BN43-202")
      )
      (libsource (lib "vitech_inductors") (part "Amidon_BN43-202"))
    )
    (comp (ref "VD1")
      (value "ES3D")
      (footprint "SMC")
      (description "Diode Standard 200V 3A, SMC")
      (fields
        (field (name "PART NUMBER") "ES3D")
        (field (name "PACKAGE") "SMC")
        (field (name "VOLTAGE") "200V")
        (field (name "MANUFACTURER") "Onsemi")
      )
      (libsource (lib "vitech_semiconductors") (part "ES3D"))
    )
    (comp (ref "VD2")
      (value "SK34SMA-3G")
      (footprint "SMA_MED")
      (description "Diode Schottky 40V 3A, SMA, Leakage Current 50uA")
      (fields
        (field (name "PART NUMBER") "SK34SMA-3G")
        (field (name "PACKAGE") "SMA")
        (field (name "VOLTAGE") "40V")
        (field (name "MANUFACTURER") "Diodec Semiconductor")
      )
      (libsource (lib "vitech_semiconductors") (part "SK34SMA-3G"))
    )
    (comp (ref "VD3")
      (value "LL4148")
      (footprint "SOD-80C_MED")
      (description "Fast Switching Diode, 100V 200 mA, SOD-80C")
      (fields
        (field (name "PART NUMBER") "LL4148")
        (field (name "VOLTAGE") "100V")
        (field (name "MANUFACTURER") "Suntan")
      )
      (libsource (lib "vitech_semiconductors") (part "LL4148"))
    )
    (comp (ref "VD4")
      (value "LL4148")
      (footprint "SOD-80C_MED")
      (description "Fast Switching Diode, 100V 200 mA, SOD-80C")
      (fields
        (field (name "PART NUMBER") "LL4148")
        (field (name "VOLTAGE") "100V")
        (field (name "MANUFACTURER") "Suntan")
      )
      (libsource (lib "vitech_semiconductors") (part "LL4148"))
    )
    (comp (ref "VD6")
      (value "LL4148")
      (footprint "SOD-80C_MED")
      (description "Fast Switching Diode, 100V 200 mA, SOD-80C")
      (fields
        (field (name "PART NUMBER") "LL4148")
        (field (name "VOLTAGE") "100V")
        (field (name "MANUFACTURER") "Suntan")
      )
      (libsource (lib "vitech_semiconductors") (part "LL4148"))
    )
    (comp (ref "VD7")
      (value "PESD12VL2BT.215")
      (footprint "SOT-23_MED")
      (description "Double Bidirectional TVS Diode 26V Clamp, 15A (8/20us) Ipp, SOT-23")
      (fields
        (field (name "PART NUMBER") "PESD12VL2BT.215")
        (field (name "MANUFACTURER") "Nexperia USA")
        (field (name "VOLTAGE") "12V")
      )
      (libsource (lib "vitech_semiconductors") (part "PESD3V3L2BT,215"))
    )
    (comp (ref "VD8")
      (value "PESD12VL2BT.215")
      (footprint "SOT-23_MED")
      (description "Double Bidirectional TVS Diode 26V Clamp, 15A (8/20us) Ipp, SOT-23")
      (fields
        (field (name "PART NUMBER") "PESD12VL2BT.215")
        (field (name "MANUFACTURER") "Nexperia USA")
        (field (name "VOLTAGE") "12V")
      )
      (libsource (lib "vitech_semiconductors") (part "PESD3V3L2BT,215"))
    )
    (comp (ref "VD10")
      (value "LL4148")
      (footprint "SOD-80C_MED")
      (description "Fast Switching Diode, 100V 200 mA, SOD-80C")
      (fields
        (field (name "PART NUMBER") "LL4148")
        (field (name "VOLTAGE") "100V")
        (field (name "MANUFACTURER") "Suntan")
      )
      (libsource (lib "vitech_semiconductors") (part "LL4148"))
    )
    (comp (ref "VT1")
      (value "MRF186")
      (footprint "MRF186")
      (description "40V, 60A max N-Channel AlphaSGT Power MOSFET, 6.1mOhm @ Vgs = 10V")
      (fields (field (name "MANUFACTURER") "MOTOROLLA") (field (name "PART NUMBER") "MRF186"))
      (libsource (lib "vitech_semiconductors") (part "MRF186"))
    )
    (comp (ref "VT2")
      (value "IRLML9303TRPbF")
      (footprint "SOT-23_MED")
      (description "-30V, -3.6A max P-Channel HEXFET MOSFET, 82mOhm @ Vgs = -4.5V")
      (fields
        (field (name "MANUFACTURER") "Infineon Technologies")
        (field (name "PART NUMBER") "IRLML9301TRPbF")
      )
      (libsource (lib "vitech_semiconductors") (part "IRLML9301TRPbF"))
    )
    (comp (ref "VT3")
      (value "IRLML0100TR")
      (footprint "SOT-23_MED")
      (description "100V, 1.6A max N-Channel HEXFET Power MOSFET, 190mOhm @ Vgs = 4.5V")
      (fields
        (field (name "PART NUMBER") "IRLML0100TRPBF")
        (field (name "VDS") "100V")
        (field (name "ID") "1.6A")
        (field (name "MANUFACTURER") "Infineon Technologies")
      )
      (libsource (lib "vitech_semiconductors") (part "IRLML0100TRPBF"))
    )
    (comp (ref "X1")
      (value "WH-03S")
      (footprint "WF-3S")
      (description "WH Series 2.54mm Wire to Board Straight DIP Type Headers, 3 Pin")
      (fields (field (name "PART NUMBER") "CI3103P1V00") (field (name "MANUFACTURER") "CviLux"))
      (libsource (lib "vitech_connectors") (part "CI3103P1V00"))
    )
    (comp (ref "X2")
      (value "WH-02R")
      (footprint "WF-2R")
      (description "WH Series 2.54mm Wire to Board Right Angle DIP Type Headers, 2 Pin")
      (fields (field (name "PART NUMBER") "TX_LED") (field (name "MANUFACTURER") "CviLux"))
      (libsource (lib "vitech_connectors") (part "CI3102P1H00"))
    )
    (comp (ref "X3")
      (value "WH-02R")
      (footprint "WF-2R")
      (description "WH Series 2.54mm Wire to Board Right Angle DIP Type Headers, 2 Pin")
      (fields (field (name "PART NUMBER") "0B_TX") (field (name "MANUFACTURER") "CviLux"))
      (libsource (lib "vitech_connectors") (part "CI3102P1H00"))
    )
    (comp (ref "X4")
      (value "WH-02R")
      (footprint "WF-2R")
      (description "WH Series 2.54mm Wire to Board Right Angle DIP Type Headers, 2 Pin")
      (fields (field (name "PART NUMBER") "ВЕНТИЛЯТОР") (field (name "MANUFACTURER") "CviLux"))
      (libsource (lib "vitech_connectors") (part "CI3102P1H00"))
    )
    (comp (ref "X5")
      (value "WH-02R")
      (footprint "WF-2R")
      (description "WH Series 2.54mm Wire to Board Right Angle DIP Type Headers, 2 Pin")
      (fields (field (name "PART NUMBER") "ТЕРМОСТАТ") (field (name "MANUFACTURER") "CviLux"))
      (libsource (lib "vitech_connectors") (part "CI3102P1H00"))
    )
    (comp (ref "X6")
      (value "WSD-SMAKWE-14.5")
      (footprint "KLS1-SMA002")
      (description "50Ohm SMA Connector, Right Angle, Female, 5.1mm")
      (fields
        (field (name "PART NUMBER") "WSD-SMAKWE-14.5")
        (field (name "MANUFACTURER") "Wangshen Development LLC")
      )
      (libsource (lib "vitech_connectors") (part "WSD-SMAKWE-14.5"))
    )
    (comp (ref "X7")
      (value "WSD-SMAKWE-14.5")
      (footprint "KLS1-SMA002")
      (description "50Ohm SMA Connector, Right Angle, Female, 5.1mm")
      (fields
        (field (name "PART NUMBER") "WSD-SMAKWE-14.5")
        (field (name "MANUFACTURER") "Wangshen Development LLC")
      )
      (libsource (lib "") (part "WSD-SMAKWE-14.5_1"))
    )
    (comp (ref "X8")
      (value "XT30PW-M")
      (footprint "XT30PW-M")
      (description "2 Pin DC Power Socket, XT30, Male, THT, Right Angle, Yellow, 15A, 500V")
      (fields (field (name "PART NUMBER") "XT30PW-M") (field (name "MANUFACTURER") "Amass"))
      (libsource (lib "vitech_connectors") (part "XT30PW-M"))
    )
    (comp (ref "X9")
      (value "WH-02R")
      (footprint "WF-2R")
      (description "WH Series 2.54mm Wire to Board Right Angle DIP Type Headers, 2 Pin")
      (fields (field (name "PART NUMBER") "cDISABLE_BIAS") (field (name "MANUFACTURER") "CviLux"))
      (libsource (lib "vitech_connectors") (part "CI3102P1H00"))
    )
    (comp (ref "Z1")
      (value "~")
      (footprint "Murata_BNX02xH01x")
      (description "LC EMI Filter 5th Order Low Pass 2 Channel C = 4.7µF 20 A 6-SMD [12.1x9.1]")
      (fields (field (name "MANUFACTURER") "Murata") (field (name "PART NUMBER") "BNX024-H01L"))
      (libsource (lib "Passive") (part "BNX024H01L"))
    )
  )
  (nets
    (net (code "1") (name "+5V_TX") (class "Default")
      (node (ref "C5") (pin "1") (pinfunction "1_1") (pintype "passive"))
      (node (ref "C6") (pin "1") (pinfunction "1_1") (pintype "passive"))
      (node (ref "FB4") (pin "1") (pintype "passive"))
      (node (ref "R1") (pin "1") (pinfunction "1_1") (pintype "passive"))
    )
    (net (code "2") (name "+12V_IN") (class "Default")
      (node (ref "C3") (pin "1") (pinfunction "1_1") (pintype "passive"))
      (node (ref "C32") (pin "1") (pinfunction "1_1") (pintype "passive"))
      (node (ref "FB1") (pin "1") (pintype "passive"))
      (node (ref "R10") (pin "2") (pinfunction "2_2") (pintype "passive"))
      (node (ref "VT2") (pin "2") (pinfunction "S_2") (pintype "passive"))
    )
    (net (code "3") (name "+12V_TX") (class "Default")
      (node (ref "C24") (pin "2") (pinfunction "2_2") (pintype "passive"))
      (node (ref "C27") (pin "2") (pinfunction "2_2") (pintype "passive"))
      (node (ref "C4") (pin "1") (pinfunction "1_1") (pintype "passive"))
      (node (ref "FB3") (pin "2") (pintype "passive"))
      (node (ref "K1") (pin "2") (pinfunction "COIL2_2") (pintype "passive"))
      (node (ref "K2") (pin "2") (pinfunction "COIL2_2") (pintype "passive"))
      (node (ref "R12") (pin "1") (pinfunction "1_1") (pintype "passive"))
      (node (ref "R16") (pin "1") (pinfunction "1_1") (pintype "passive"))
      (node (ref "R9") (pin "2") (pinfunction "2_2") (pintype "passive"))
      (node (ref "VD10") (pin "CA") (pintype "passive"))
      (node (ref "VD6") (pin "CA") (pintype "passive"))
      (node (ref "VT2") (pin "3") (pinfunction "D_3") (pintype "passive"))
    )
    (net (code "4") (name "+24V_IN") (class "Default")
      (node (ref "C1") (pin "2") (pinfunction "2_2") (pintype "passive"))
      (node (ref "C11") (pin "1") (pinfunction "1_1") (pintype "passive"))
      (node (ref "C12") (pin "1") (pinfunction "1_1") (pintype "passive"))
      (node (ref "C13") (pin "1") (pinfunction "1_1") (pintype "passive"))
      (node (ref "C14") (pin "1") (pinfunction "1_1") (pintype "passive"))
      (node (ref "C16") (pin "1") (pinfunction "1_1") (pintype "passive"))
      (node (ref "C2") (pin "1") (pinfunction "1_1") (pintype "passive"))
      (node (ref "L1") (pin "1") (pinfunction "1_1") (pintype "passive"))
      (node (ref "R27") (pin "1") (pinfunction "1_1") (pintype "passive"))
      (node (ref "TP6") (pin "1") (pintype "passive"))
      (node (ref "TR1") (pin "4") (pintype "passive"))
    )
    (net (code "5") (name "+V_FAN") (class "Default")
      (node (ref "C31") (pin "1") (pinfunction "1_1") (pintype "passive"))
      (node (ref "C33") (pin "1") (pinfunction "1_1") (pintype "passive"))
      (node (ref "FB2") (pin "1") (pintype "passive"))
      (node (ref "R28") (pin "1") (pinfunction "1_1") (pintype "passive"))
      (node (ref "X4") (pin "1") (pinfunction "1_1") (pintype "passive"))
    )
    (net (code "6") (name "BIAS_A") (class "Default")
      (node (ref "C18") (pin "1") (pinfunction "1_1") (pintype "passive"))
      (node (ref "C8") (pin "1") (pinfunction "1_1") (pintype "passive"))
      (node (ref "R18") (pin "1") (pinfunction "1_1") (pintype "passive"))
      (node (ref "R7") (pin "2") (pinfunction "WIPER_2") (pintype "passive"))
    )
    (net (code "7") (name "BIAS_B") (class "Default")
      (node (ref "C19") (pin "1") (pinfunction "1_1") (pintype "passive"))
      (node (ref "C9") (pin "1") (pinfunction "1_1") (pintype "passive"))
      (node (ref "R19") (pin "1") (pinfunction "1_1") (pintype "passive"))
      (node (ref "R8") (pin "2") (pinfunction "WIPER_2") (pintype "passive"))
    )
    (net (code "8") (name "GND") (class "Default")
      (node (ref "C1") (pin "1") (pinfunction "1_1") (pintype "passive"))
      (node (ref "C10") (pin "2") (pinfunction "2_2") (pintype "passive"))
      (node (ref "C11") (pin "2") (pinfunction "2_2") (pintype "passive"))
      (node (ref "C12") (pin "2") (pinfunction "2_2") (pintype "passive"))
      (node (ref "C13") (pin "2") (pinfunction "2_2") (pintype "passive"))
      (node (ref "C14") (pin "2") (pinfunction "2_2") (pintype "passive"))
      (node (ref "C16") (pin "2") (pinfunction "2_2") (pintype "passive"))
      (node (ref "C18") (pin "2") (pinfunction "2_2") (pintype "passive"))
      (node (ref "C19") (pin "2") (pinfunction "2_2") (pintype "passive"))
      (node (ref "C2") (pin "2") (pinfunction "2_2") (pintype "passive"))
      (node (ref "C22") (pin "2") (pinfunction "2_2") (pintype "passive"))
      (node (ref "C24") (pin "1") (pinfunction "1_1") (pintype "passive"))
      (node (ref "C27") (pin "1") (pinfunction "1_1") (pintype "passive"))
      (node (ref "C3") (pin "2") (pinfunction "2_2") (pintype "passive"))
      (node (ref "C31") (pin "2") (pinfunction "2_2") (pintype "passive"))
      (node (ref "C32") (pin "2") (pinfunction "2_2") (pintype "passive"))
      (node (ref "C33") (pin "2") (pinfunction "2_2") (pintype "passive"))
      (node (ref "C4") (pin "2") (pinfunction "2_2") (pintype "passive"))
      (node (ref "C5") (pin "2") (pinfunction "2_2") (pintype "passive"))
      (node (ref "C6") (pin "2") (pinfunction "2_2") (pintype "passive"))
      (node (ref "C7") (pin "2") (pinfunction "2_2") (pintype "passive"))
      (node (ref "C8") (pin "2") (pinfunction "2_2") (pintype "passive"))
      (node (ref "C9") (pin "2") (pinfunction "2_2") (pintype "passive"))
      (node (ref "D3") (pin "3") (pinfunction "GND_3") (pintype "passive"))
      (node (ref "D3") (pin "5") (pinfunction "~{ON/}OFF_5") (pintype "passive"))
      (node (ref "D3") (pin "6") (pinfunction "TP_6") (pintype "passive"))
      (node (ref "D4") (pin "3") (pinfunction "GND(TAB)_3") (pintype "passive"))
      (node (ref "HG1") (pin "CA") (pinfunction "Cathode_CA") (pintype "passive"))
      (node (ref "HG2") (pin "CA") (pinfunction "Cathode_CA") (pintype "passive"))
      (node (ref "HG3") (pin "CA") (pinfunction "Cathode_CA") (pintype "passive"))
      (node (ref "HG4") (pin "CA") (pinfunction "Cathode_CA") (pintype "passive"))
      (node (ref "K1") (pin "1") (pinfunction "COIL1_1") (pintype "passive"))
      (node (ref "K2") (pin "1") (pinfunction "COIL1_1") (pintype "passive"))
      (node (ref "R14") (pin "1") (pinfunction "1_1") (pintype "passive"))
      (node (ref "R17") (pin "1") (pinfunction "1_1") (pintype "passive"))
      (node (ref "R2") (pin "2") (pinfunction "2_2") (pintype "passive"))
      (node (ref "R23") (pin "1") (pinfunction "1_1") (pintype "passive"))
      (node (ref "R32") (pin "2") (pinfunction "2_2") (pintype "passive"))
      (node (ref "R5") (pin "1") (pinfunction "1_1") (pintype "passive"))
      (node (ref "R7") (pin "3") (pinfunction "CW_3") (pintype "passive"))
      (node (ref "R8") (pin "3") (pinfunction "CW_3") (pintype "passive"))
      (node (ref "TR1") (pin "1") (pintype "passive"))
      (node (ref "TR2") (pin "1") (pintype "passive"))
      (node (ref "VD10") (pin "AN") (pintype "passive"))
      (node (ref "VD2") (pin "AN") (pintype "passive"))
      (node (ref "VD6") (pin "AN") (pintype "passive"))
      (node (ref "VD7") (pin "1") (pintype "passive"))
      (node (ref "VD7") (pin "2") (pintype "passive"))
      (node (ref "VD8") (pin "1") (pintype "passive"))
      (node (ref "VD8") (pin "2") (pintype "passive"))
      (node (ref "VT1") (pin "5") (pinfunction "S_5") (pintype "passive"))
      (node (ref "VT3") (pin "2") (pinfunction "S_2") (pintype "passive"))
      (node (ref "X1") (pin "2") (pinfunction "2_2") (pintype "passive"))
      (node (ref "X1") (pin "3") (pinfunction "3_3") (pintype "passive"))
      (node (ref "X2") (pin "2") (pinfunction "2_2") (pintype "passive"))
      (node (ref "X3") (pin "2") (pinfunction "2_2") (pintype "passive"))
      (node (ref "X5") (pin "2") (pinfunction "2_2") (pintype "passive"))
      (node (ref "X6") (pin "2") (pinfunction "2_2") (pintype "passive"))
      (node (ref "X7") (pin "2") (pinfunction "2_2") (pintype "passive"))
      (node (ref "X9") (pin "2") (pinfunction "2_2") (pintype "passive"))
      (node (ref "Z1") (pin "4") (pinfunction "OUT-_4") (pintype "passive"))
      (node (ref "Z1") (pin "5") (pinfunction "OUT-_5") (pintype "passive"))
      (node (ref "Z1") (pin "6") (pinfunction "OUT-_6") (pintype "passive"))
    )
    (net (code "9") (name "GND_IN") (class "Default")
      (node (ref "VD1") (pin "AN") (pintype "passive"))
      (node (ref "X8") (pin "2") (pinfunction "2_2") (pintype "passive"))
      (node (ref "X8") (pin "MP") (pinfunction "MP_MP") (pintype "passive"))
      (node (ref "Z1") (pin "3") (pinfunction "IN-_3") (pintype "passive"))
    )
    (net (code "10") (name "Net-(C10-Pad1)") (class "Default")
      (node (ref "C10") (pin "1") (pinfunction "1_1") (pintype "passive"))
      (node (ref "FB2") (pin "2") (pintype "passive"))
      (node (ref "L4") (pin "2") (pinfunction "2_2") (pintype "passive"))
      (node (ref "R30") (pin "1") (pinfunction "1_1") (pintype "passive"))
    )
    (net (code "11") (name "Net-(C20-Pad1)") (class "Default")
      (node (ref "C20") (pin "1") (pinfunction "1_1") (pintype "passive"))
      (node (ref "TR2") (pin "4") (pintype "passive"))
    )
    (net (code "12") (name "Net-(C20-Pad2)") (class "Default")
      (node (ref "C20") (pin "2") (pinfunction "2_2") (pintype "passive"))
      (node (ref "R20") (pin "1") (pinfunction "1_1") (pintype "passive"))
    )
    (net (code "13") (name "Net-(C21-Pad2)") (class "Default")
      (node (ref "C21") (pin "2") (pinfunction "2_2") (pintype "passive"))
      (node (ref "R21") (pin "1") (pinfunction "1_1") (pintype "passive"))
    )
    (net (code "14") (name "Net-(C25-Pad1)") (class "Default")
      (node (ref "C25") (pin "1") (pinfunction "1_1") (pintype "passive"))
      (node (ref "TR2") (pin "3") (pintype "passive"))
    )
    (net (code "15") (name "Net-(C25-Pad2)") (class "Default")
      (node (ref "C25") (pin "2") (pinfunction "2_2") (pintype "passive"))
      (node (ref "R26") (pin "1") (pinfunction "1_1") (pintype "passive"))
    )
    (net (code "16") (name "Net-(C26-Pad1)") (class "Default")
      (node (ref "C26") (pin "1") (pinfunction "1_1") (pintype "passive"))
      (node (ref "TR1") (pin "3") (pintype "passive"))
      (node (ref "VT1") (pin "2") (pinfunction "S_2") (pintype "passive"))
    )
    (net (code "17") (name "Net-(C26-Pad2)") (class "Default")
      (node (ref "C26") (pin "2") (pinfunction "2_2") (pintype "passive"))
      (node (ref "R22") (pin "1") (pinfunction "1_1") (pintype "passive"))
    )
    (net (code "18") (name "Net-(D1-ADJ)") (class "Default")
      (node (ref "D1") (pin "1") (pinfunction "ADJ_1") (pintype "passive"))
      (node (ref "R3") (pin "1") (pinfunction "1_1") (pintype "passive"))
      (node (ref "R5") (pin "2") (pinfunction "2_2") (pintype "passive"))
    )
    (net (code "19") (name "Net-(D1-VIN)") (class "Default")
      (node (ref "D1") (pin "3") (pinfunction "VIN_3") (pintype "passive"))
      (node (ref "FB5") (pin "1") (pintype "passive"))
    )
    (net (code "20") (name "Net-(D1-VOUT)") (class "Default")
      (node (ref "D1") (pin "2") (pinfunction "VOUT_2") (pintype "passive"))
      (node (ref "FB1") (pin "2") (pintype "passive"))
      (node (ref "R3") (pin "2") (pinfunction "2_2") (pintype "passive"))
    )
    (net (code "21") (name "Net-(D2-A)") (class "Default")
      (node (ref "D2") (pin "3") (pinfunction "A_3") (pintype "passive"))
      (node (ref "R6") (pin "2") (pinfunction "2_2") (pintype "passive"))
      (node (ref "X1") (pin "1") (pinfunction "1_1") (pintype "passive"))
    )
    (net (code "22") (name "Net-(D2-C)") (class "Default")
      (node (ref "D2") (pin "1") (pinfunction "C_1") (pintype "passive"))
      (node (ref "R1") (pin "2") (pinfunction "2_2") (pintype "passive"))
      (node (ref "R4") (pin "1") (pinfunction "1_1") (pintype "passive"))
      (node (ref "R7") (pin "1") (pinfunction "CCW_1") (pintype "passive"))
      (node (ref "R8") (pin "1") (pinfunction "CCW_1") (pintype "passive"))
    )
    (net (code "23") (name "Net-(D2-REF)") (class "Default")
      (node (ref "D2") (pin "2") (pinfunction "REF_2") (pintype "passive"))
      (node (ref "R4") (pin "2") (pinfunction "2_2") (pintype "passive"))
      (node (ref "R6") (pin "1") (pinfunction "1_1") (pintype "passive"))
    )
    (net (code "24") (name "Net-(D3-FB)") (class "Default")
      (node (ref "D3") (pin "4") (pinfunction "FB_4") (pintype "passive"))
      (node (ref "R2") (pin "1") (pinfunction "1_1") (pintype "passive"))
      (node (ref "R30") (pin "2") (pinfunction "2_2") (pintype "passive"))
    )
    (net (code "25") (name "Net-(D3-Vin)") (class "Default")
      (node (ref "C22") (pin "1") (pinfunction "1_1") (pintype "passive"))
      (node (ref "D3") (pin "1") (pinfunction "Vin_1") (pintype "passive"))
      (node (ref "FB6") (pin "1") (pintype "passive"))
    )
    (net (code "26") (name "Net-(D3-Vout)") (class "Default")
      (node (ref "D3") (pin "2") (pinfunction "Vout_2") (pintype "passive"))
      (node (ref "L4") (pin "1") (pinfunction "1_1") (pintype "passive"))
      (node (ref "VD2") (pin "CA") (pintype "passive"))
    )
    (net (code "27") (name "Net-(D4-ADJ)") (class "Default")
      (node (ref "D4") (pin "5") (pinfunction "ADJ_5") (pintype "passive"))
      (node (ref "R31") (pin "2") (pinfunction "2_2") (pintype "passive"))
      (node (ref "R32") (pin "1") (pinfunction "1_1") (pintype "passive"))
    )
    (net (code "28") (name "Net-(D4-EN)") (class "Default")
      (node (ref "D4") (pin "1") (pinfunction "EN_1") (pintype "passive"))
      (node (ref "R25") (pin "2") (pinfunction "2_2") (pintype "passive"))
      (node (ref "R29") (pin "1") (pinfunction "1_1") (pintype "passive"))
    )
    (net (code "29") (name "Net-(D4-VIN)") (class "Default")
      (node (ref "D4") (pin "2") (pinfunction "VIN_2") (pintype "passive"))
      (node (ref "FB3") (pin "1") (pintype "passive"))
      (node (ref "R25") (pin "1") (pinfunction "1_1") (pintype "passive"))
    )
    (net (code "30") (name "Net-(D4-VOUT)") (class "Default")
      (node (ref "D4") (pin "4") (pinfunction "VOUT_4") (pintype "passive"))
      (node (ref "FB4") (pin "2") (pintype "passive"))
      (node (ref "R11") (pin "2") (pinfunction "2_2") (pintype "passive"))
      (node (ref "R31") (pin "1") (pinfunction "1_1") (pintype "passive"))
    )
    (net (code "31") (name "Net-(F1-Pad1)") (class "Default")
      (node (ref "F1") (pin "1") (pinfunction "1_1") (pintype "passive"))
      (node (ref "X8") (pin "1") (pinfunction "1_1") (pintype "passive"))
    )
    (net (code "32") (name "Net-(FB7-Pad2)") (class "Default")
      (node (ref "FB7") (pin "2") (pintype "passive"))
      (node (ref "X4") (pin "2") (pinfunction "2_2") (pintype "passive"))
      (node (ref "X5") (pin "1") (pinfunction "1_1") (pintype "passive"))
    )
    (net (code "33") (name "Net-(HG1-Anode)") (class "Default")
      (node (ref "HG1") (pin "AN") (pinfunction "Anode_AN") (pintype "passive"))
      (node (ref "R11") (pin "1") (pinfunction "1_1") (pintype "passive"))
    )
    (net (code "34") (name "Net-(HG2-Anode)") (class "Default")
      (node (ref "HG2") (pin "AN") (pinfunction "Anode_AN") (pintype "passive"))
      (node (ref "R12") (pin "2") (pinfunction "2_2") (pintype "passive"))
    )
    (net (code "35") (name "Net-(HG3-Anode)") (class "Default")
      (node (ref "HG3") (pin "AN") (pinfunction "Anode_AN") (pintype "passive"))
      (node (ref "R27") (pin "2") (pinfunction "2_2") (pintype "passive"))
    )
    (net (code "36") (name "Net-(HG4-Anode)") (class "Default")
      (node (ref "HG4") (pin "AN") (pinfunction "Anode_AN") (pintype "passive"))
      (node (ref "R28") (pin "2") (pinfunction "2_2") (pintype "passive"))
    )
    (net (code "37") (name "Net-(K1-1-COM)") (class "Default")
      (node (ref "K1") (pin "5") (pinfunction "1-COM_5") (pintype "passive"))
      (node (ref "K1") (pin "6") (pinfunction "2-COM_6") (pintype "passive"))
      (node (ref "X6") (pin "1") (pinfunction "1_1") (pintype "passive"))
    )
    (net (code "38") (name "Net-(K1-1-NC)") (class "Default")
      (node (ref "K1") (pin "3") (pinfunction "1-NC_3") (pintype "passive"))
      (node (ref "K1") (pin "4") (pinfunction "2-NC_4") (pintype "passive"))
      (node (ref "K2") (pin "3") (pinfunction "1-NC_3") (pintype "passive"))
      (node (ref "K2") (pin "4") (pinfunction "2-NC_4") (pintype "passive"))
    )
    (net (code "39") (name "Net-(K1-2-NO-Pad7)") (class "Default")
      (node (ref "K1") (pin "7") (pinfunction "2-NO_7") (pintype "passive"))
      (node (ref "K1") (pin "8") (pinfunction "2-NO_8") (pintype "passive"))
      (node (ref "TR1") (pin "2") (pintype "passive"))
    )
    (net (code "40") (name "Net-(K2-1-COM)") (class "Default")
      (node (ref "K2") (pin "5") (pinfunction "1-COM_5") (pintype "passive"))
      (node (ref "K2") (pin "6") (pinfunction "2-COM_6") (pintype "passive"))
      (node (ref "X7") (pin "1") (pinfunction "1_1") (pintype "passive"))
    )
    (net (code "41") (name "Net-(K2-2-NO-Pad7)") (class "Default")
      (node (ref "K2") (pin "7") (pinfunction "2-NO_7") (pintype "passive"))
      (node (ref "K2") (pin "8") (pinfunction "2-NO_8") (pintype "passive"))
      (node (ref "R13") (pin "1") (pinfunction "1_1") (pintype "passive"))
      (node (ref "R14") (pin "2") (pinfunction "2_2") (pintype "passive"))
    )
    (net (code "42") (name "Net-(R9-Pad1)") (class "Default")
      (node (ref "R9") (pin "1") (pinfunction "1_1") (pintype "passive"))
      (node (ref "X2") (pin "1") (pinfunction "1_1") (pintype "passive"))
    )
    (net (code "43") (name "Net-(R13-Pad2)") (class "Default")
      (node (ref "R13") (pin "2") (pinfunction "2_2") (pintype "passive"))
      (node (ref "R23") (pin "2") (pinfunction "2_2") (pintype "passive"))
      (node (ref "TR2") (pin "2") (pintype "passive"))
    )
    (net (code "44") (name "Net-(R15-Pad2)") (class "Default")
      (node (ref "R15") (pin "2") (pinfunction "2_2") (pintype "passive"))
      (node (ref "VD3") (pin "AN") (pintype "passive"))
    )
    (net (code "45") (name "Net-(R18-Pad2)") (class "Default")
      (node (ref "R18") (pin "2") (pinfunction "2_2") (pintype "passive"))
      (node (ref "R20") (pin "2") (pinfunction "2_2") (pintype "passive"))
      (node (ref "R21") (pin "2") (pinfunction "2_2") (pintype "passive"))
      (node (ref "R24") (pin "2") (pinfunction "2_2") (pintype "passive"))
      (node (ref "VD7") (pin "3") (pintype "passive"))
      (node (ref "VT1") (pin "3") (pinfunction "G_3") (pintype "passive"))
    )
    (net (code "46") (name "Net-(R19-Pad2)") (class "Default")
      (node (ref "R19") (pin "2") (pinfunction "2_2") (pintype "passive"))
      (node (ref "R22") (pin "2") (pinfunction "2_2") (pintype "passive"))
      (node (ref "R24") (pin "1") (pinfunction "1_1") (pintype "passive"))
      (node (ref "R26") (pin "2") (pinfunction "2_2") (pintype "passive"))
      (node (ref "VD8") (pin "3") (pintype "passive"))
      (node (ref "VT1") (pin "4") (pinfunction "G_4") (pintype "passive"))
    )
    (net (code "47") (name "Net-(R29-Pad2)") (class "Default")
      (node (ref "R29") (pin "2") (pinfunction "2_2") (pintype "passive"))
      (node (ref "VD4") (pin "AN") (pintype "passive"))
    )
    (net (code "48") (name "Net-(VD3-PadCA)") (class "Default")
      (node (ref "VD3") (pin "CA") (pintype "passive"))
      (node (ref "X3") (pin "1") (pinfunction "1_1") (pintype "passive"))
    )
    (net (code "49") (name "Net-(VD4-PadCA)") (class "Default")
      (node (ref "VD4") (pin "CA") (pintype "passive"))
      (node (ref "X9") (pin "1") (pinfunction "1_1") (pintype "passive"))
    )
    (net (code "50") (name "Net-(VT1-D)") (class "Default")
      (node (ref "C21") (pin "1") (pinfunction "1_1") (pintype "passive"))
      (node (ref "TR1") (pin "5") (pintype "passive"))
      (node (ref "VT1") (pin "1") (pinfunction "D_1") (pintype "passive"))
    )
    (net (code "51") (name "Net-(VT2-G)") (class "Default")
      (node (ref "C7") (pin "1") (pinfunction "1_1") (pintype "passive"))
      (node (ref "R10") (pin "1") (pinfunction "1_1") (pintype "passive"))
      (node (ref "R15") (pin "1") (pinfunction "1_1") (pintype "passive"))
      (node (ref "VT2") (pin "1") (pinfunction "G_1") (pintype "passive"))
    )
    (net (code "52") (name "Net-(VT3-D)") (class "Default")
      (node (ref "FB7") (pin "1") (pintype "passive"))
      (node (ref "VT3") (pin "3") (pinfunction "D_3") (pintype "passive"))
    )
    (net (code "53") (name "Net-(VT3-G)") (class "Default")
      (node (ref "R16") (pin "2") (pinfunction "2_2") (pintype "passive"))
      (node (ref "R17") (pin "2") (pinfunction "2_2") (pintype "passive"))
      (node (ref "VT3") (pin "1") (pinfunction "G_1") (pintype "passive"))
    )
    (net (code "54") (name "Net-(Z1-IN+)") (class "Default")
      (node (ref "F1") (pin "2") (pinfunction "2_2") (pintype "passive"))
      (node (ref "VD1") (pin "CA") (pintype "passive"))
      (node (ref "Z1") (pin "1") (pinfunction "IN+_1") (pintype "passive"))
    )
    (net (code "55") (name "Net-(Z1-OUT+)") (class "Default")
      (node (ref "FB5") (pin "2") (pintype "passive"))
      (node (ref "FB6") (pin "2") (pintype "passive"))
      (node (ref "L1") (pin "2") (pinfunction "2_2") (pintype "passive"))
      (node (ref "Z1") (pin "2") (pinfunction "OUT+_2") (pintype "passive"))
    )
  )
)
